# softstart.net
KiCad netlist of a schematic drawn in EAGLE
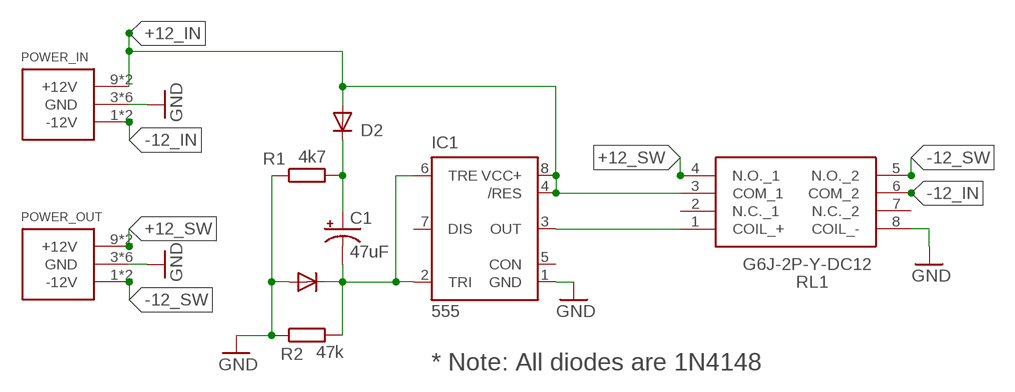
[diagram p0: schematic, sheet 1]

(export (version "E")
  (design (tool "Eeschema 10.0.6"))
  (components
    (comp (ref "C1")
      (value "47uF")
      (footprint "eagle-import:TT2D6")
      (libsource (lib "eagle-import") (part "CPOL-USTT2D6"))
    )
    (comp (ref "D1")
      (value "1N4001")
      (footprint "eagle-import:SMALL_DIODE")
      (libsource (lib "eagle-import") (part "SMALL_DIODEDO35-7"))
    )
    (comp (ref "D2")
      (value "SMALL_DIODEDO35-7")
      (footprint "eagle-import:SMALL_DIODE")
      (libsource (lib "eagle-import") (part "SMALL_DIODEDO35-7"))
    )
    (comp (ref "IC1")
      (value "555")
      (footprint "eagle-import:DIP08")
      (libsource (lib "eagle-import") (part "555P"))
    )
    (comp (ref "POWER_IN")
      (value "RUSS_EURORACK_POWER_SIMPLE10")
      (footprint "eagle-import:RUSS_EURORACK_POWER_10")
      (libsource (lib "eagle-import") (part "RUSS_EURORACK_POWER_SIMPLE10"))
    )
    (comp (ref "POWER_OUT")
      (value "RUSS_EURORACK_POWER_SIMPLE10")
      (footprint "eagle-import:RUSS_EURORACK_POWER_10")
      (libsource (lib "eagle-import") (part "RUSS_EURORACK_POWER_SIMPLE10"))
    )
    (comp (ref "R1")
      (value "4k7")
      (footprint "eagle-import:7MM_RESISTOR")
      (libsource (lib "eagle-import") (part "RESISTOR7MM"))
    )
    (comp (ref "R2")
      (value "47k")
      (footprint "eagle-import:7MM_RESISTOR")
      (libsource (lib "eagle-import") (part "RESISTOR7MM"))
    )
    (comp (ref "RL1")
      (value "G6J-2P-Y-DC12")
      (footprint "eagle-import:G6J2PYDC12")
      (fields (field (name "MOUSER_PART_NUMBER") "653-G6J-2P-Y-DC12"))
      (libsource (lib "eagle-import") (part "G6J-2P-Y-DC12"))
    )
  )
  (nets
    (net (code "1") (name "+12_IN") (class "Default")
      (node (ref "D2") (pin "A") (pinfunction "A_A") (pintype "passive"))
      (node (ref "IC1") (pin "4") (pinfunction "/RES_4") (pintype "input"))
      (node (ref "IC1") (pin "8") (pinfunction "VCC+_8") (pintype "power_in"))
      (node (ref "POWER_IN") (pin "10") (pinfunction "+12V_10") (pintype "bidirectional"))
      (node (ref "POWER_IN") (pin "9") (pinfunction "+12V_9") (pintype "bidirectional"))
      (node (ref "RL1") (pin "3") (pinfunction "COM_1_3") (pintype "bidirectional"))
    )
    (net (code "2") (name "+12_SW") (class "Default")
      (node (ref "POWER_OUT") (pin "10") (pinfunction "+12V_10") (pintype "bidirectional"))
      (node (ref "POWER_OUT") (pin "9") (pinfunction "+12V_9") (pintype "bidirectional"))
      (node (ref "RL1") (pin "4") (pinfunction "N.O._1_4") (pintype "bidirectional"))
    )
    (net (code "3") (name "-12_IN") (class "Default")
      (node (ref "POWER_IN") (pin "1") (pinfunction "-12V_1") (pintype "bidirectional"))
      (node (ref "POWER_IN") (pin "2") (pinfunction "-12V_2") (pintype "bidirectional"))
      (node (ref "RL1") (pin "6") (pinfunction "COM_2_6") (pintype "bidirectional"))
    )
    (net (code "4") (name "-12_SW") (class "Default")
      (node (ref "POWER_OUT") (pin "1") (pinfunction "-12V_1") (pintype "bidirectional"))
      (node (ref "POWER_OUT") (pin "2") (pinfunction "-12V_2") (pintype "bidirectional"))
      (node (ref "RL1") (pin "5") (pinfunction "N.O._2_5") (pintype "bidirectional"))
    )
    (net (code "5") (name "GND") (class "Default")
      (node (ref "D1") (pin "A") (pinfunction "A_A") (pintype "passive"))
      (node (ref "IC1") (pin "1") (pinfunction "GND_1") (pintype "power_in"))
      (node (ref "POWER_IN") (pin "3") (pinfunction "GND_3") (pintype "bidirectional"))
      (node (ref "POWER_IN") (pin "4") (pinfunction "GND_4") (pintype "bidirectional"))
      (node (ref "POWER_IN") (pin "5") (pinfunction "GND_5") (pintype "bidirectional"))
      (node (ref "POWER_IN") (pin "6") (pinfunction "GND_6") (pintype "bidirectional"))
      (node (ref "POWER_IN") (pin "7") (pinfunction "GND_7") (pintype "bidirectional"))
      (node (ref "POWER_IN") (pin "8") (pinfunction "GND_8") (pintype "bidirectional"))
      (node (ref "POWER_OUT") (pin "3") (pinfunction "GND_3") (pintype "bidirectional"))
      (node (ref "POWER_OUT") (pin "4") (pinfunction "GND_4") (pintype "bidirectional"))
      (node (ref "POWER_OUT") (pin "5") (pinfunction "GND_5") (pintype "bidirectional"))
      (node (ref "POWER_OUT") (pin "6") (pinfunction "GND_6") (pintype "bidirectional"))
      (node (ref "POWER_OUT") (pin "7") (pinfunction "GND_7") (pintype "bidirectional"))
      (node (ref "POWER_OUT") (pin "8") (pinfunction "GND_8") (pintype "bidirectional"))
      (node (ref "R1") (pin "1") (pinfunction "1_1") (pintype "passive"))
      (node (ref "R2") (pin "1") (pinfunction "1_1") (pintype "passive"))
      (node (ref "RL1") (pin "8") (pinfunction "COIL_-_8") (pintype "bidirectional"))
    )
    (net (code "6") (name "Net-(C1-Pad+)") (class "Default")
      (node (ref "C1") (pin "+") (pinfunction "+_+") (pintype "passive"))
      (node (ref "D2") (pin "C") (pinfunction "C_C") (pintype "passive"))
      (node (ref "R1") (pin "2") (pinfunction "2_2") (pintype "passive"))
    )
    (net (code "7") (name "Net-(IC1-OUT)") (class "Default")
      (node (ref "IC1") (pin "3") (pinfunction "OUT_3") (pintype "output"))
      (node (ref "RL1") (pin "1") (pinfunction "COIL_+_1") (pintype "bidirectional"))
    )
    (net (code "8") (name "Net-(IC1-TRE)") (class "Default")
      (node (ref "C1") (pin "-") (pinfunction "-_-") (pintype "passive"))
      (node (ref "D1") (pin "C") (pinfunction "C_C") (pintype "passive"))
      (node (ref "IC1") (pin "2") (pinfunction "TRI_2") (pintype "input"))
      (node (ref "IC1") (pin "6") (pinfunction "TRE_6") (pintype "input"))
      (node (ref "R2") (pin "2") (pinfunction "2_2") (pintype "passive"))
    )
    (net (code "9") (name "unconnected-(IC1-CON-Pad5)") (class "Default")
      (node (ref "IC1") (pin "5") (pinfunction "CON_5") (pintype "input"))
    )
    (net (code "10") (name "unconnected-(IC1-DIS-Pad7)") (class "Default")
      (node (ref "IC1") (pin "7") (pinfunction "DIS_7") (pintype "input"))
    )
    (net (code "11") (name "unconnected-(RL1-N.C._1-Pad2)") (class "Default")
      (node (ref "RL1") (pin "2") (pinfunction "N.C._1_2") (pintype "bidirectional"))
    )
    (net (code "12") (name "unconnected-(RL1-N.C._2-Pad7)") (class "Default")
      (node (ref "RL1") (pin "7") (pinfunction "N.C._2_7") (pintype "bidirectional"))
    )
  )
)
